# Schematic_Attiny_85_Flashhat.net
KiCad netlist of a schematic drawn in EasyEDA
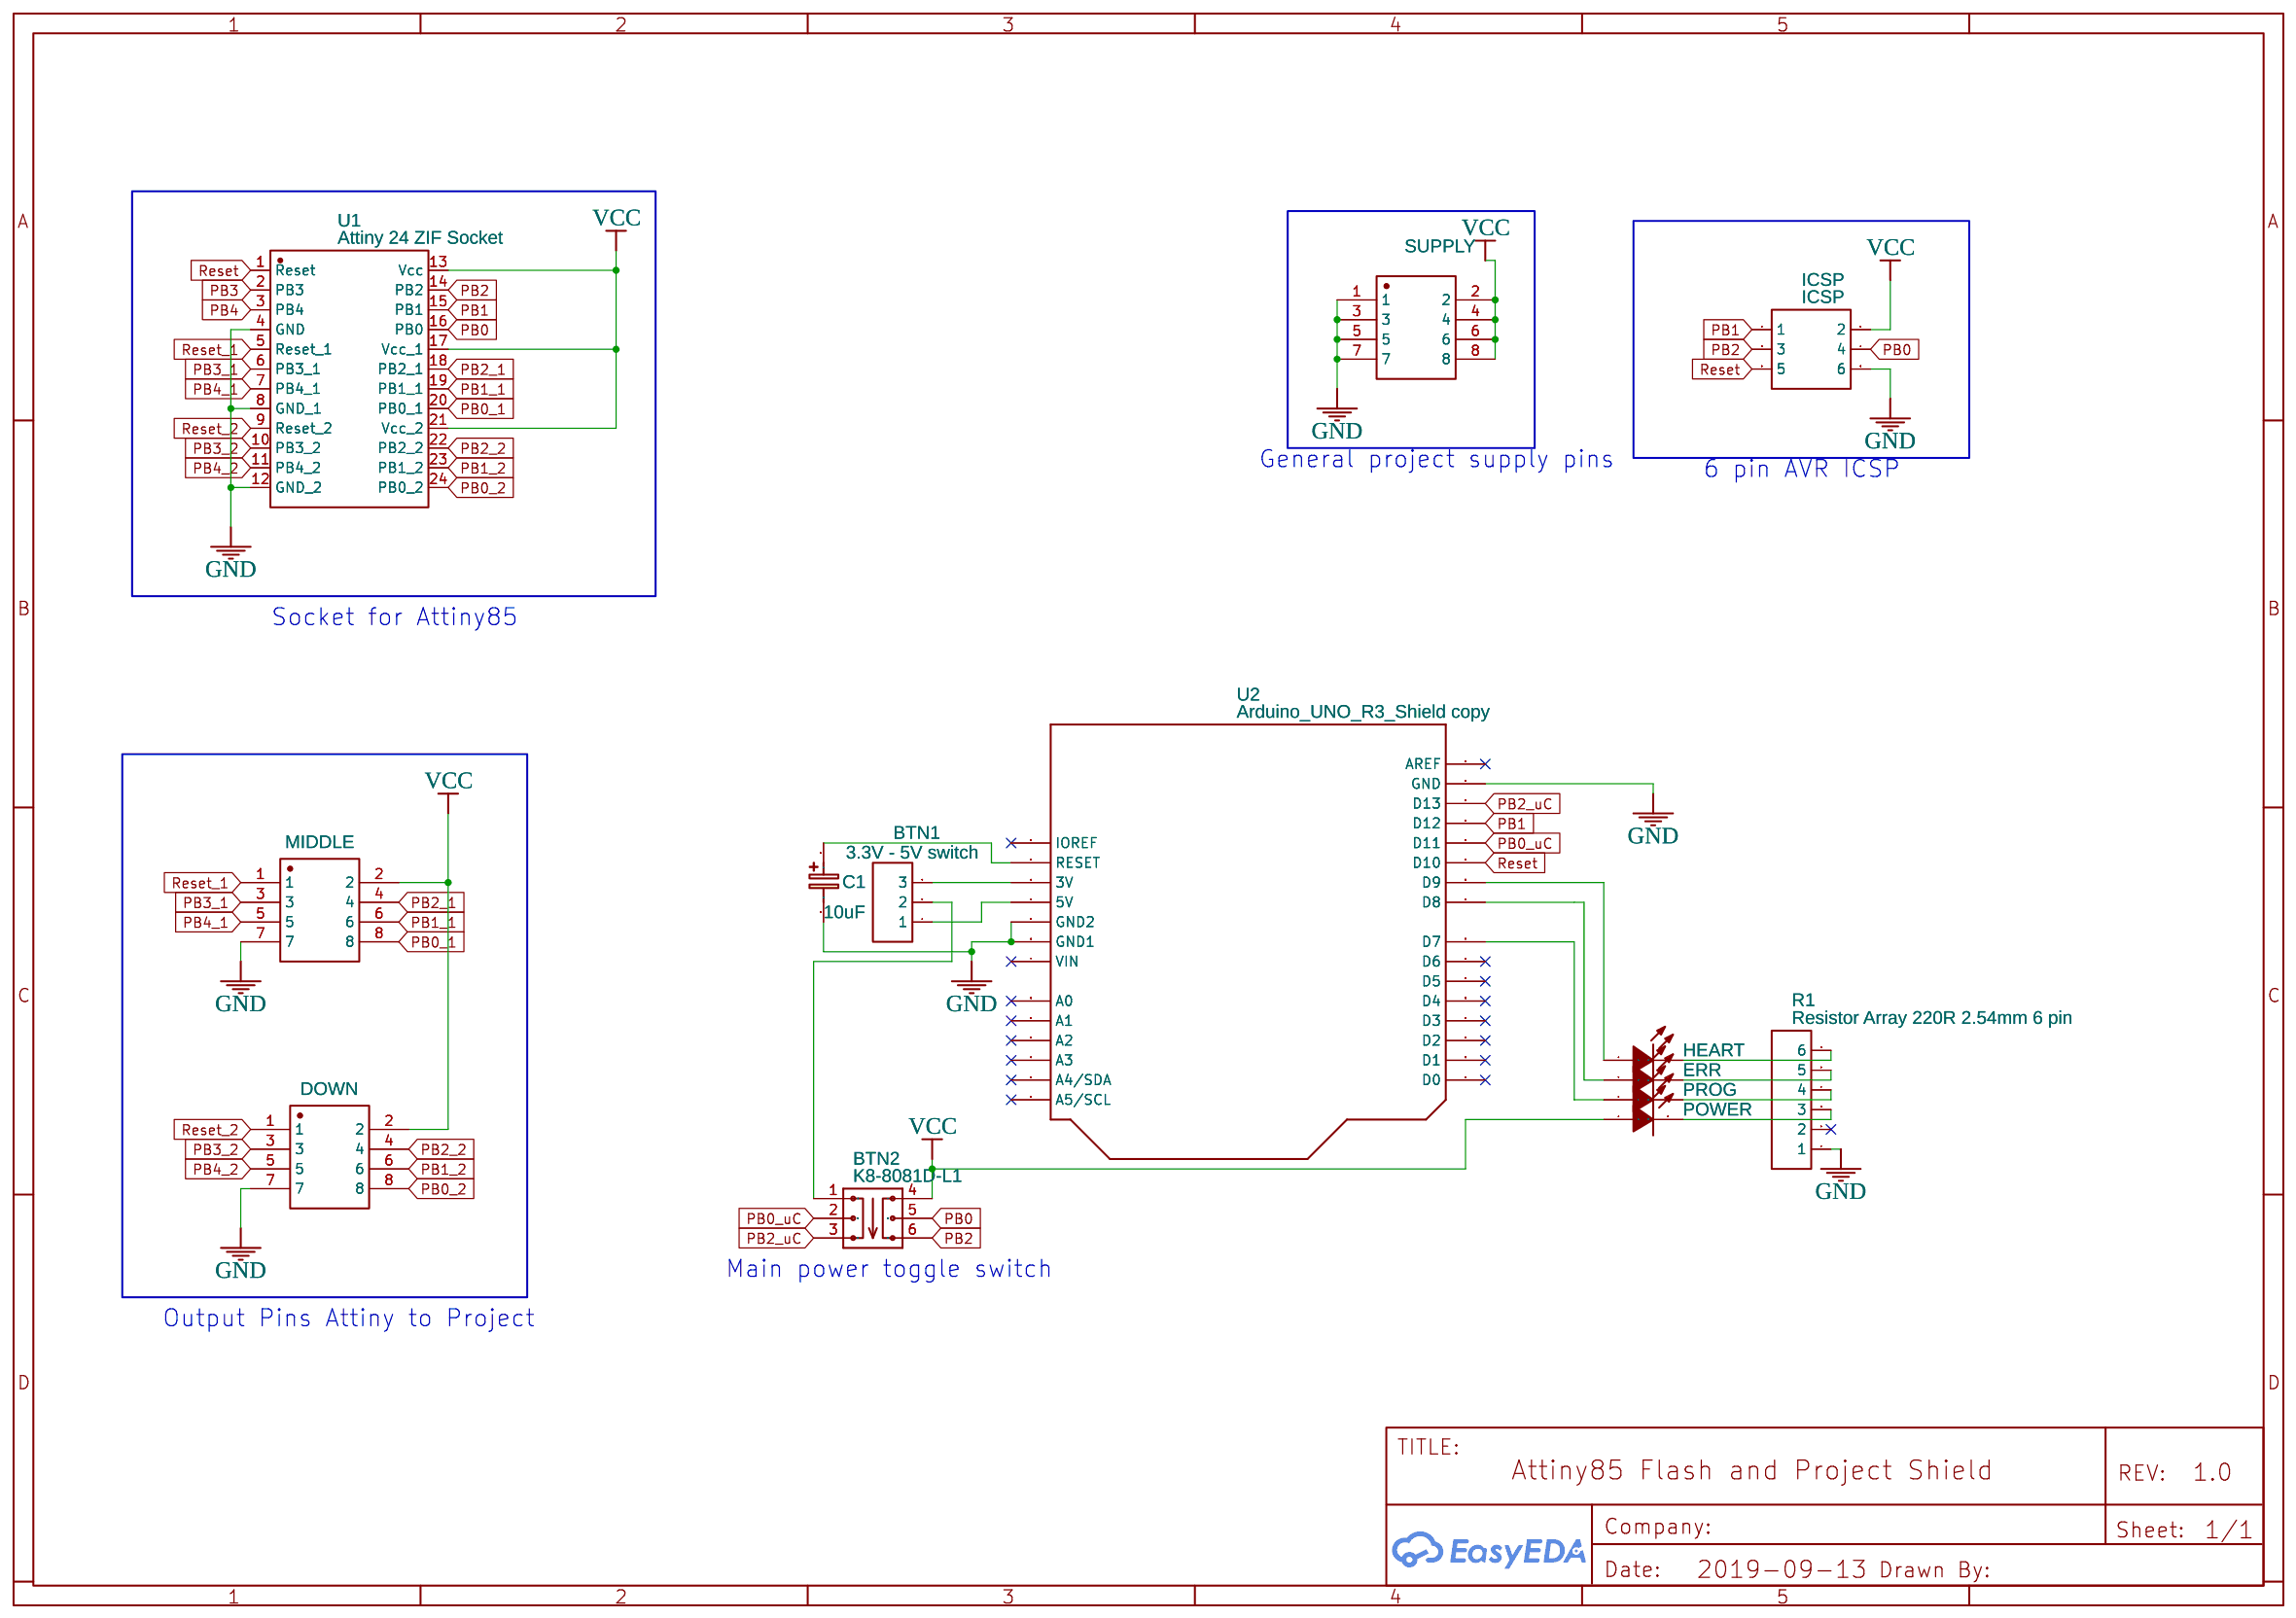
[diagram p0: schematic sheet]

(export (version "E")
  (design (tool "Eeschema 10.0.6"))
  (components
    (comp (ref "BTN1")
      (value "3.3V - 5V switch")
      (fields
        (field (name "BOM_Manufacturer Part") "Header2.54mm 1*3P")
        (field (name "BOM_Supplier Part") "C49257")
      )
      (libsource (lib "") (part "Unknown_450_450"))
    )
    (comp (ref "BTN2")
      (value "K8-8081D-L1")
      (fields (field (name "BOM_Supplier Part") "C124009"))
      (libsource (lib "") (part "Unknown_435_610"))
    )
    (comp (ref "C1") (value "10uF") (libsource (lib "") (part "Cap_Electrolytic(TH)_D3.0XF1.5_EU")))
    (comp (ref "DOWN")
      (value "210S-2*4P L=11.6MMGold-plated black")
      (fields (field (name "BOM_Supplier Part") "C124386"))
      (libsource (lib "") (part "Unknown_160_580"))
    )
    (comp (ref "ERR")
      (value "17-21SURC/S530-A2/TR8")
      (fields (field (name "BOM_Supplier Part") "C131244"))
      (libsource (lib "") (part "Unknown_825_535"))
    )
    (comp (ref "HEART")
      (value "17-21SURC/S530-A2/TR8")
      (fields (field (name "BOM_Supplier Part") "C131244"))
      (libsource (lib "") (part "Unknown_825_525"))
    )
    (comp (ref "ICSP")
      (value "ICSP")
      (fields
        (field (name "BOM_Manufacturer Part") "Header-Male-2.54_2x3")
        (field (name "BOM_Supplier Part") "C65114")
      )
      (libsource (lib "") (part "Unknown_910_170"))
    )
    (comp (ref "MIDDLE")
      (value "210S-2*4P L=11.6MMGold-plated black")
      (fields (field (name "BOM_Supplier Part") "C124386"))
      (libsource (lib "") (part "Unknown_155_455"))
    )
    (comp (ref "POWER")
      (value "17-21SURC/S530-A2/TR8")
      (fields (field (name "BOM_Supplier Part") "C131244"))
      (libsource (lib "") (part "Unknown_825_555"))
    )
    (comp (ref "PROG")
      (value "17-21SURC/S530-A2/TR8")
      (fields (field (name "BOM_Supplier Part") "C131244"))
      (libsource (lib "") (part "Unknown_825_545"))
    )
    (comp (ref "R1")
      (value "Resistor Array 220R 2.54mm 6 pin")
      (fields
        (field (name "BOM_Manufacturer Part") "Header-Male-2.54_1x6")
        (field (name "BOM_Supplier Part") "C37208")
      )
      (libsource (lib "") (part "Unknown_905_550"))
    )
    (comp (ref "SUPPLY")
      (value "210S-2*4P L=11.6MMGold-plated black")
      (fields (field (name "BOM_Supplier Part") "C124386"))
      (libsource (lib "") (part "Unknown_710_160"))
    )
    (comp (ref "U1") (value "Attiny 24 ZIF Socket") (libsource (lib "") (part "Unknown_150_185")))
    (comp (ref "U2")
      (value "Arduino_UNO_R3_Shield copy")
      (fields (field (name "BOM_Manufacturer Part") "Arduino_UNO_R3_Shield"))
      (libsource (lib "") (part "Unknown_625_450"))
    )
  )
  (nets
    (net (code "1") (name "GND") (class "Default")
      (node (ref "C1") (pin "2") (pinfunction "2_2") (pintype "unspecified"))
      (node (ref "DOWN") (pin "7") (pinfunction "7_7") (pintype "unspecified"))
      (node (ref "ICSP") (pin "6") (pinfunction "6_6") (pintype "input"))
      (node (ref "MIDDLE") (pin "7") (pinfunction "7_7") (pintype "unspecified"))
      (node (ref "R1") (pin "1") (pinfunction "1_1") (pintype "input"))
      (node (ref "SUPPLY") (pin "1") (pinfunction "1_1") (pintype "unspecified"))
      (node (ref "SUPPLY") (pin "3") (pinfunction "3_3") (pintype "unspecified"))
      (node (ref "SUPPLY") (pin "5") (pinfunction "5_5") (pintype "unspecified"))
      (node (ref "SUPPLY") (pin "7") (pinfunction "7_7") (pintype "unspecified"))
      (node (ref "U1") (pin "12") (pinfunction "GND_2_12") (pintype "unspecified"))
      (node (ref "U1") (pin "4") (pinfunction "GND_4") (pintype "unspecified"))
      (node (ref "U1") (pin "8") (pinfunction "GND_1_8") (pintype "unspecified"))
      (node (ref "U2") (pin "28") (pinfunction "GND_28") (pintype "passive"))
      (node (ref "U2") (pin "5") (pinfunction "GND2_5") (pintype "passive"))
      (node (ref "U2") (pin "6") (pinfunction "GND1_6") (pintype "passive"))
    )
    (net (code "2") (name "Net-(BTN1-Pad2)") (class "Default")
      (node (ref "BTN1") (pin "2") (pinfunction "2_2") (pintype "input"))
      (node (ref "BTN2") (pin "1") (pinfunction "1_1") (pintype "unspecified"))
    )
    (net (code "3") (name "Net-(ERR-A)") (class "Default")
      (node (ref "ERR") (pin "1") (pinfunction "A_1") (pintype "unspecified"))
      (node (ref "U2") (pin "22") (pinfunction "D8_22") (pintype "unspecified"))
    )
    (net (code "4") (name "Net-(ERR-K)") (class "Default")
      (node (ref "ERR") (pin "2") (pinfunction "K_2") (pintype "unspecified"))
      (node (ref "R1") (pin "5") (pinfunction "5_5") (pintype "input"))
    )
    (net (code "5") (name "Net-(HEART-A)") (class "Default")
      (node (ref "HEART") (pin "1") (pinfunction "A_1") (pintype "unspecified"))
      (node (ref "U2") (pin "23") (pinfunction "D9_23") (pintype "unspecified"))
    )
    (net (code "6") (name "Net-(HEART-K)") (class "Default")
      (node (ref "HEART") (pin "2") (pinfunction "K_2") (pintype "unspecified"))
      (node (ref "R1") (pin "6") (pinfunction "6_6") (pintype "input"))
    )
    (net (code "7") (name "Net-(POWER-K)") (class "Default")
      (node (ref "POWER") (pin "2") (pinfunction "K_2") (pintype "unspecified"))
      (node (ref "R1") (pin "3") (pinfunction "3_3") (pintype "input"))
    )
    (net (code "8") (name "Net-(PROG-A)") (class "Default")
      (node (ref "PROG") (pin "1") (pinfunction "A_1") (pintype "unspecified"))
      (node (ref "U2") (pin "21") (pinfunction "D7_21") (pintype "unspecified"))
    )
    (net (code "9") (name "Net-(PROG-K)") (class "Default")
      (node (ref "PROG") (pin "2") (pinfunction "K_2") (pintype "unspecified"))
      (node (ref "R1") (pin "4") (pinfunction "4_4") (pintype "input"))
    )
    (net (code "10") (name "Net-(U2-3V)") (class "Default")
      (node (ref "BTN1") (pin "3") (pinfunction "3_3") (pintype "input"))
      (node (ref "U2") (pin "3") (pinfunction "3V_3") (pintype "passive"))
    )
    (net (code "11") (name "Net-(U2-5V)") (class "Default")
      (node (ref "BTN1") (pin "1") (pinfunction "1_1") (pintype "input"))
      (node (ref "U2") (pin "4") (pinfunction "5V_4") (pintype "passive"))
    )
    (net (code "12") (name "Net-(U2-RESET)") (class "Default")
      (node (ref "C1") (pin "1") (pinfunction "1_1") (pintype "unspecified"))
      (node (ref "U2") (pin "2") (pinfunction "RESET_2") (pintype "unspecified"))
    )
    (net (code "13") (name "PB0") (class "Default")
      (node (ref "BTN2") (pin "5") (pinfunction "5_5") (pintype "unspecified"))
      (node (ref "ICSP") (pin "4") (pinfunction "4_4") (pintype "input"))
      (node (ref "U1") (pin "16") (pinfunction "PB0_16") (pintype "unspecified"))
    )
    (net (code "14") (name "PB0_1") (class "Default")
      (node (ref "MIDDLE") (pin "8") (pinfunction "8_8") (pintype "unspecified"))
      (node (ref "U1") (pin "20") (pinfunction "PB0_1_20") (pintype "unspecified"))
    )
    (net (code "15") (name "PB0_2") (class "Default")
      (node (ref "DOWN") (pin "8") (pinfunction "8_8") (pintype "unspecified"))
      (node (ref "U1") (pin "24") (pinfunction "PB0_2_24") (pintype "unspecified"))
    )
    (net (code "16") (name "PB0_uC") (class "Default")
      (node (ref "BTN2") (pin "2") (pinfunction "2_2") (pintype "unspecified"))
      (node (ref "U2") (pin "25") (pinfunction "D11_25") (pintype "unspecified"))
    )
    (net (code "17") (name "PB1") (class "Default")
      (node (ref "ICSP") (pin "1") (pinfunction "1_1") (pintype "input"))
      (node (ref "U1") (pin "15") (pinfunction "PB1_15") (pintype "unspecified"))
      (node (ref "U2") (pin "26") (pinfunction "D12_26") (pintype "unspecified"))
    )
    (net (code "18") (name "PB1_1") (class "Default")
      (node (ref "MIDDLE") (pin "6") (pinfunction "6_6") (pintype "unspecified"))
      (node (ref "U1") (pin "19") (pinfunction "PB1_1_19") (pintype "unspecified"))
    )
    (net (code "19") (name "PB1_2") (class "Default")
      (node (ref "DOWN") (pin "6") (pinfunction "6_6") (pintype "unspecified"))
      (node (ref "U1") (pin "23") (pinfunction "PB1_2_23") (pintype "unspecified"))
    )
    (net (code "20") (name "PB2") (class "Default")
      (node (ref "BTN2") (pin "6") (pinfunction "6_6") (pintype "unspecified"))
      (node (ref "ICSP") (pin "3") (pinfunction "3_3") (pintype "input"))
      (node (ref "U1") (pin "14") (pinfunction "PB2_14") (pintype "unspecified"))
    )
    (net (code "21") (name "PB2_1") (class "Default")
      (node (ref "MIDDLE") (pin "4") (pinfunction "4_4") (pintype "unspecified"))
      (node (ref "U1") (pin "18") (pinfunction "PB2_1_18") (pintype "unspecified"))
    )
    (net (code "22") (name "PB2_2") (class "Default")
      (node (ref "DOWN") (pin "4") (pinfunction "4_4") (pintype "unspecified"))
      (node (ref "U1") (pin "22") (pinfunction "PB2_2_22") (pintype "unspecified"))
    )
    (net (code "23") (name "PB2_uC") (class "Default")
      (node (ref "BTN2") (pin "3") (pinfunction "3_3") (pintype "unspecified"))
      (node (ref "U2") (pin "27") (pinfunction "D13_27") (pintype "unspecified"))
    )
    (net (code "24") (name "PB3") (class "Default")
      (node (ref "U1") (pin "2") (pinfunction "PB3_2") (pintype "unspecified"))
    )
    (net (code "25") (name "PB3_1") (class "Default")
      (node (ref "MIDDLE") (pin "3") (pinfunction "3_3") (pintype "unspecified"))
      (node (ref "U1") (pin "6") (pinfunction "PB3_1_6") (pintype "unspecified"))
    )
    (net (code "26") (name "PB3_2") (class "Default")
      (node (ref "DOWN") (pin "3") (pinfunction "3_3") (pintype "unspecified"))
      (node (ref "U1") (pin "10") (pinfunction "PB3_2_10") (pintype "unspecified"))
    )
    (net (code "27") (name "PB4") (class "Default")
      (node (ref "U1") (pin "3") (pinfunction "PB4_3") (pintype "unspecified"))
    )
    (net (code "28") (name "PB4_1") (class "Default")
      (node (ref "MIDDLE") (pin "5") (pinfunction "5_5") (pintype "unspecified"))
      (node (ref "U1") (pin "7") (pinfunction "PB4_1_7") (pintype "unspecified"))
    )
    (net (code "29") (name "PB4_2") (class "Default")
      (node (ref "DOWN") (pin "5") (pinfunction "5_5") (pintype "unspecified"))
      (node (ref "U1") (pin "11") (pinfunction "PB4_2_11") (pintype "unspecified"))
    )
    (net (code "30") (name "Reset") (class "Default")
      (node (ref "ICSP") (pin "5") (pinfunction "5_5") (pintype "input"))
      (node (ref "U1") (pin "1") (pinfunction "Reset_1") (pintype "unspecified"))
      (node (ref "U2") (pin "24") (pinfunction "D10_24") (pintype "unspecified"))
    )
    (net (code "31") (name "Reset_1") (class "Default")
      (node (ref "MIDDLE") (pin "1") (pinfunction "1_1") (pintype "unspecified"))
      (node (ref "U1") (pin "5") (pinfunction "Reset_1_5") (pintype "unspecified"))
    )
    (net (code "32") (name "Reset_2") (class "Default")
      (node (ref "DOWN") (pin "1") (pinfunction "1_1") (pintype "unspecified"))
      (node (ref "U1") (pin "9") (pinfunction "Reset_2_9") (pintype "unspecified"))
    )
    (net (code "33") (name "VCC") (class "Default")
      (node (ref "BTN2") (pin "4") (pinfunction "4_4") (pintype "unspecified"))
      (node (ref "DOWN") (pin "2") (pinfunction "2_2") (pintype "unspecified"))
      (node (ref "ICSP") (pin "2") (pinfunction "2_2") (pintype "input"))
      (node (ref "MIDDLE") (pin "2") (pinfunction "2_2") (pintype "unspecified"))
      (node (ref "POWER") (pin "1") (pinfunction "A_1") (pintype "unspecified"))
      (node (ref "SUPPLY") (pin "2") (pinfunction "2_2") (pintype "unspecified"))
      (node (ref "SUPPLY") (pin "4") (pinfunction "4_4") (pintype "unspecified"))
      (node (ref "SUPPLY") (pin "6") (pinfunction "6_6") (pintype "unspecified"))
      (node (ref "SUPPLY") (pin "8") (pinfunction "8_8") (pintype "unspecified"))
      (node (ref "U1") (pin "13") (pinfunction "Vcc_13") (pintype "unspecified"))
      (node (ref "U1") (pin "17") (pinfunction "Vcc_1_17") (pintype "unspecified"))
      (node (ref "U1") (pin "21") (pinfunction "Vcc_2_21") (pintype "unspecified"))
    )
    (net (code "34") (name "unconnected-(R1-Pad2)") (class "Default")
      (node (ref "R1") (pin "2") (pinfunction "2_2") (pintype "input+no_connect"))
    )
    (net (code "35") (name "unconnected-(U2-A0-Pad8)") (class "Default")
      (node (ref "U2") (pin "8") (pinfunction "A0_8") (pintype "unspecified+no_connect"))
    )
    (net (code "36") (name "unconnected-(U2-A1-Pad9)") (class "Default")
      (node (ref "U2") (pin "9") (pinfunction "A1_9") (pintype "unspecified+no_connect"))
    )
    (net (code "37") (name "unconnected-(U2-A2-Pad10)") (class "Default")
      (node (ref "U2") (pin "10") (pinfunction "A2_10") (pintype "unspecified+no_connect"))
    )
    (net (code "38") (name "unconnected-(U2-A3-Pad11)") (class "Default")
      (node (ref "U2") (pin "11") (pinfunction "A3_11") (pintype "unspecified+no_connect"))
    )
    (net (code "39") (name "unconnected-(U2-A4{slash}SDA-Pad12)") (class "Default")
      (node (ref "U2") (pin "12") (pinfunction "A4/SDA_12") (pintype "unspecified+no_connect"))
    )
    (net (code "40") (name "unconnected-(U2-A5{slash}SCL-Pad13)") (class "Default")
      (node (ref "U2") (pin "13") (pinfunction "A5/SCL_13") (pintype "unspecified+no_connect"))
    )
    (net (code "41") (name "unconnected-(U2-AREF-Pad29)") (class "Default")
      (node (ref "U2") (pin "29") (pinfunction "AREF_29") (pintype "unspecified+no_connect"))
    )
    (net (code "42") (name "unconnected-(U2-D0-Pad14)") (class "Default")
      (node (ref "U2") (pin "14") (pinfunction "D0_14") (pintype "unspecified+no_connect"))
    )
    (net (code "43") (name "unconnected-(U2-D1-Pad15)") (class "Default")
      (node (ref "U2") (pin "15") (pinfunction "D1_15") (pintype "unspecified+no_connect"))
    )
    (net (code "44") (name "unconnected-(U2-D2-Pad16)") (class "Default")
      (node (ref "U2") (pin "16") (pinfunction "D2_16") (pintype "unspecified+no_connect"))
    )
    (net (code "45") (name "unconnected-(U2-D3-Pad17)") (class "Default")
      (node (ref "U2") (pin "17") (pinfunction "D3_17") (pintype "unspecified+no_connect"))
    )
    (net (code "46") (name "unconnected-(U2-D4-Pad18)") (class "Default")
      (node (ref "U2") (pin "18") (pinfunction "D4_18") (pintype "unspecified+no_connect"))
    )
    (net (code "47") (name "unconnected-(U2-D5-Pad19)") (class "Default")
      (node (ref "U2") (pin "19") (pinfunction "D5_19") (pintype "unspecified+no_connect"))
    )
    (net (code "48") (name "unconnected-(U2-D6-Pad20)") (class "Default")
      (node (ref "U2") (pin "20") (pinfunction "D6_20") (pintype "unspecified+no_connect"))
    )
    (net (code "49") (name "unconnected-(U2-IOREF-Pad1)") (class "Default")
      (node (ref "U2") (pin "1") (pinfunction "IOREF_1") (pintype "unspecified+no_connect"))
    )
    (net (code "50") (name "unconnected-(U2-VIN-Pad7)") (class "Default")
      (node (ref "U2") (pin "7") (pinfunction "VIN_7") (pintype "passive+no_connect"))
    )
  )
)
